# Greenhouse_Schematics.net
KiCad netlist of a schematic drawn in EAGLE
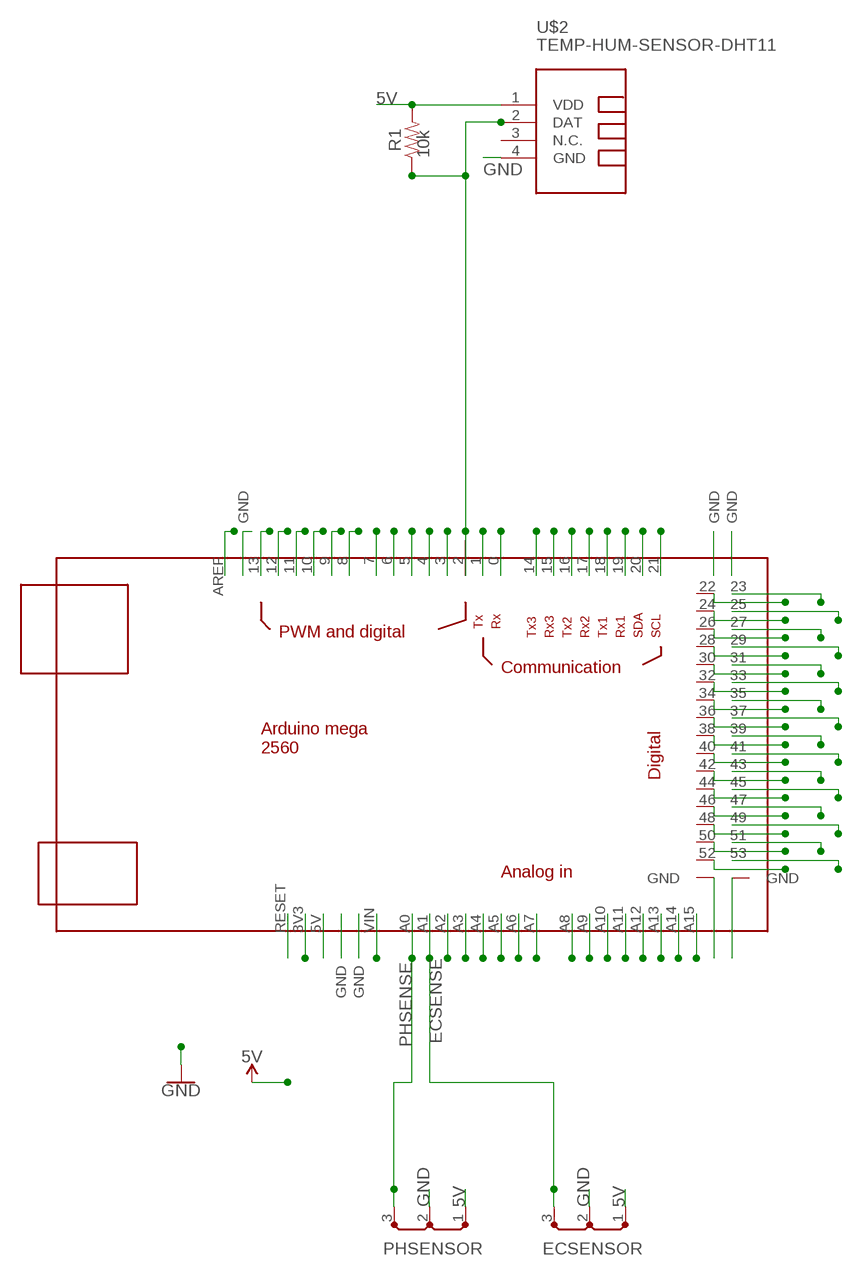
[diagram p0: schematic, sheet 1]

(export (version "E")
  (design (tool "Eeschema 10.0.6"))
  (components
    (comp (ref "BB1")
      (value "TE4/3")
      (footprint "eagle-import:TE4_3")
      (libsource (lib "eagle-import") (part "TE4/3"))
    )
    (comp (ref "BB2")
      (value "TE4/3")
      (footprint "eagle-import:TE4_3")
      (libsource (lib "eagle-import") (part "TE4/3"))
    )
    (comp (ref "R1")
      (value "RESISTORAXIAL-0.3")
      (footprint "eagle-import:AXIAL-0.3")
      (fields (field (name "PROD_ID") "10k"))
      (libsource (lib "eagle-import") (part "RESISTORAXIAL-0.3"))
    )
    (comp (ref "U$1")
      (value "MEGA_DEVICE")
      (footprint "eagle-import:MEGABOX")
      (libsource (lib "eagle-import") (part "MEGA_DEVICE"))
    )
    (comp (ref "U$2")
      (value "TEMP-HUM-SENSOR-DHT11")
      (footprint "eagle-import:TEMP-HUM-SENSOR-DHT11")
      (libsource (lib "eagle-import") (part "TEMP-HUM-SENSOR-DHT11"))
    )
  )
  (nets
    (net (code "1") (name "/ECSENSE") (class "Default")
      (node (ref "BB2") (pin "3") (pinfunction "P_3") (pintype "passive"))
      (node (ref "U$1") (pin "A1") (pinfunction "A1_A1") (pintype "bidirectional"))
    )
    (net (code "2") (name "/PHSENSE") (class "Default")
      (node (ref "BB1") (pin "3") (pinfunction "P_3") (pintype "passive"))
      (node (ref "U$1") (pin "A0") (pinfunction "A0_A0") (pintype "bidirectional"))
    )
    (net (code "3") (name "5V") (class "Default")
      (node (ref "BB1") (pin "1") (pinfunction "P_1") (pintype "passive"))
      (node (ref "BB2") (pin "1") (pinfunction "P_1") (pintype "passive"))
      (node (ref "R1") (pin "P$2") (pinfunction "2_P$2") (pintype "passive"))
      (node (ref "U$1") (pin "5V") (pinfunction "5V_5V") (pintype "bidirectional"))
      (node (ref "U$2") (pin "1") (pinfunction "VDD_1") (pintype "power_in"))
    )
    (net (code "4") (name "GND") (class "Default")
      (node (ref "BB1") (pin "2") (pinfunction "P_2") (pintype "passive"))
      (node (ref "BB2") (pin "2") (pinfunction "P_2") (pintype "passive"))
      (node (ref "U$1") (pin "GND@1") (pinfunction "GND_GND@1") (pintype "bidirectional"))
      (node (ref "U$1") (pin "GND@2") (pinfunction "GND_GND@2") (pintype "bidirectional"))
      (node (ref "U$1") (pin "GND@3") (pinfunction "GND_GND@3") (pintype "bidirectional"))
      (node (ref "U$1") (pin "GND@4") (pinfunction "GND_GND@4") (pintype "bidirectional"))
      (node (ref "U$1") (pin "GND@5") (pinfunction "GND_GND@5") (pintype "bidirectional"))
      (node (ref "U$1") (pin "GND@6") (pinfunction "GND_GND@6") (pintype "bidirectional"))
      (node (ref "U$1") (pin "GND@7") (pinfunction "GND_GND@7") (pintype "bidirectional"))
      (node (ref "U$2") (pin "4") (pinfunction "GND_4") (pintype "power_in"))
    )
    (net (code "5") (name "Net-(R1-1)") (class "Default")
      (node (ref "R1") (pin "P$1") (pinfunction "1_P$1") (pintype "passive"))
      (node (ref "U$1") (pin "2") (pinfunction "2_2") (pintype "bidirectional"))
      (node (ref "U$2") (pin "2") (pinfunction "DAT_2") (pintype "bidirectional"))
    )
    (net (code "6") (name "unconnected-(U$1-Pad0)") (class "Default")
      (node (ref "U$1") (pin "0") (pinfunction "0_0") (pintype "bidirectional"))
    )
    (net (code "7") (name "unconnected-(U$1-Pad1)") (class "Default")
      (node (ref "U$1") (pin "1") (pinfunction "1_1") (pintype "bidirectional"))
    )
    (net (code "8") (name "unconnected-(U$1-Pad3)") (class "Default")
      (node (ref "U$1") (pin "3") (pinfunction "3_3") (pintype "bidirectional"))
    )
    (net (code "9") (name "unconnected-(U$1-Pad3V3)") (class "Default")
      (node (ref "U$1") (pin "3V3") (pinfunction "3V3_3V3") (pintype "bidirectional"))
    )
    (net (code "10") (name "unconnected-(U$1-Pad4)") (class "Default")
      (node (ref "U$1") (pin "4") (pinfunction "4_4") (pintype "bidirectional"))
    )
    (net (code "11") (name "unconnected-(U$1-Pad5)") (class "Default")
      (node (ref "U$1") (pin "5") (pinfunction "5_5") (pintype "bidirectional"))
    )
    (net (code "12") (name "unconnected-(U$1-Pad6)") (class "Default")
      (node (ref "U$1") (pin "6") (pinfunction "6_6") (pintype "bidirectional"))
    )
    (net (code "13") (name "unconnected-(U$1-Pad7)") (class "Default")
      (node (ref "U$1") (pin "7") (pinfunction "7_7") (pintype "bidirectional"))
    )
    (net (code "14") (name "unconnected-(U$1-Pad8)") (class "Default")
      (node (ref "U$1") (pin "8") (pinfunction "8_8") (pintype "bidirectional"))
    )
    (net (code "15") (name "unconnected-(U$1-Pad9)") (class "Default")
      (node (ref "U$1") (pin "9") (pinfunction "9_9") (pintype "bidirectional"))
    )
    (net (code "16") (name "unconnected-(U$1-Pad10)") (class "Default")
      (node (ref "U$1") (pin "10") (pinfunction "10_10") (pintype "bidirectional"))
    )
    (net (code "17") (name "unconnected-(U$1-Pad11)") (class "Default")
      (node (ref "U$1") (pin "11") (pinfunction "11_11") (pintype "bidirectional"))
    )
    (net (code "18") (name "unconnected-(U$1-Pad12)") (class "Default")
      (node (ref "U$1") (pin "12") (pinfunction "12_12") (pintype "bidirectional"))
    )
    (net (code "19") (name "unconnected-(U$1-Pad13)") (class "Default")
      (node (ref "U$1") (pin "13") (pinfunction "13_13") (pintype "bidirectional"))
    )
    (net (code "20") (name "unconnected-(U$1-Pad14)") (class "Default")
      (node (ref "U$1") (pin "14") (pinfunction "14_14") (pintype "bidirectional"))
    )
    (net (code "21") (name "unconnected-(U$1-Pad15)") (class "Default")
      (node (ref "U$1") (pin "15") (pinfunction "15_15") (pintype "bidirectional"))
    )
    (net (code "22") (name "unconnected-(U$1-Pad16)") (class "Default")
      (node (ref "U$1") (pin "16") (pinfunction "16_16") (pintype "bidirectional"))
    )
    (net (code "23") (name "unconnected-(U$1-Pad17)") (class "Default")
      (node (ref "U$1") (pin "17") (pinfunction "17_17") (pintype "bidirectional"))
    )
    (net (code "24") (name "unconnected-(U$1-Pad18)") (class "Default")
      (node (ref "U$1") (pin "18") (pinfunction "18_18") (pintype "bidirectional"))
    )
    (net (code "25") (name "unconnected-(U$1-Pad19)") (class "Default")
      (node (ref "U$1") (pin "19") (pinfunction "19_19") (pintype "bidirectional"))
    )
    (net (code "26") (name "unconnected-(U$1-Pad20)") (class "Default")
      (node (ref "U$1") (pin "20") (pinfunction "20_20") (pintype "bidirectional"))
    )
    (net (code "27") (name "unconnected-(U$1-Pad21)") (class "Default")
      (node (ref "U$1") (pin "21") (pinfunction "21_21") (pintype "bidirectional"))
    )
    (net (code "28") (name "unconnected-(U$1-Pad22)") (class "Default")
      (node (ref "U$1") (pin "22") (pinfunction "22_22") (pintype "bidirectional"))
    )
    (net (code "29") (name "unconnected-(U$1-Pad23)") (class "Default")
      (node (ref "U$1") (pin "23") (pinfunction "23_23") (pintype "bidirectional"))
    )
    (net (code "30") (name "unconnected-(U$1-Pad24)") (class "Default")
      (node (ref "U$1") (pin "24") (pinfunction "24_24") (pintype "bidirectional"))
    )
    (net (code "31") (name "unconnected-(U$1-Pad25)") (class "Default")
      (node (ref "U$1") (pin "25") (pinfunction "25_25") (pintype "bidirectional"))
    )
    (net (code "32") (name "unconnected-(U$1-Pad26)") (class "Default")
      (node (ref "U$1") (pin "26") (pinfunction "26_26") (pintype "bidirectional"))
    )
    (net (code "33") (name "unconnected-(U$1-Pad27)") (class "Default")
      (node (ref "U$1") (pin "27") (pinfunction "27_27") (pintype "bidirectional"))
    )
    (net (code "34") (name "unconnected-(U$1-Pad28)") (class "Default")
      (node (ref "U$1") (pin "28") (pinfunction "28_28") (pintype "bidirectional"))
    )
    (net (code "35") (name "unconnected-(U$1-Pad29)") (class "Default")
      (node (ref "U$1") (pin "29") (pinfunction "29_29") (pintype "bidirectional"))
    )
    (net (code "36") (name "unconnected-(U$1-Pad30)") (class "Default")
      (node (ref "U$1") (pin "30") (pinfunction "30_30") (pintype "bidirectional"))
    )
    (net (code "37") (name "unconnected-(U$1-Pad31)") (class "Default")
      (node (ref "U$1") (pin "31") (pinfunction "31_31") (pintype "bidirectional"))
    )
    (net (code "38") (name "unconnected-(U$1-Pad32)") (class "Default")
      (node (ref "U$1") (pin "32") (pinfunction "32_32") (pintype "bidirectional"))
    )
    (net (code "39") (name "unconnected-(U$1-Pad33)") (class "Default")
      (node (ref "U$1") (pin "33") (pinfunction "33_33") (pintype "bidirectional"))
    )
    (net (code "40") (name "unconnected-(U$1-Pad34)") (class "Default")
      (node (ref "U$1") (pin "34") (pinfunction "34_34") (pintype "bidirectional"))
    )
    (net (code "41") (name "unconnected-(U$1-Pad35)") (class "Default")
      (node (ref "U$1") (pin "35") (pinfunction "35_35") (pintype "bidirectional"))
    )
    (net (code "42") (name "unconnected-(U$1-Pad36)") (class "Default")
      (node (ref "U$1") (pin "36") (pinfunction "36_36") (pintype "bidirectional"))
    )
    (net (code "43") (name "unconnected-(U$1-Pad37)") (class "Default")
      (node (ref "U$1") (pin "37") (pinfunction "37_37") (pintype "bidirectional"))
    )
    (net (code "44") (name "unconnected-(U$1-Pad38)") (class "Default")
      (node (ref "U$1") (pin "38") (pinfunction "38_38") (pintype "bidirectional"))
    )
    (net (code "45") (name "unconnected-(U$1-Pad39)") (class "Default")
      (node (ref "U$1") (pin "39") (pinfunction "39_39") (pintype "bidirectional"))
    )
    (net (code "46") (name "unconnected-(U$1-Pad40)") (class "Default")
      (node (ref "U$1") (pin "40") (pinfunction "40_40") (pintype "bidirectional"))
    )
    (net (code "47") (name "unconnected-(U$1-Pad41)") (class "Default")
      (node (ref "U$1") (pin "41") (pinfunction "41_41") (pintype "bidirectional"))
    )
    (net (code "48") (name "unconnected-(U$1-Pad42)") (class "Default")
      (node (ref "U$1") (pin "42") (pinfunction "42_42") (pintype "bidirectional"))
    )
    (net (code "49") (name "unconnected-(U$1-Pad43)") (class "Default")
      (node (ref "U$1") (pin "43") (pinfunction "43_43") (pintype "bidirectional"))
    )
    (net (code "50") (name "unconnected-(U$1-Pad44)") (class "Default")
      (node (ref "U$1") (pin "44") (pinfunction "44_44") (pintype "bidirectional"))
    )
    (net (code "51") (name "unconnected-(U$1-Pad45)") (class "Default")
      (node (ref "U$1") (pin "45") (pinfunction "45_45") (pintype "bidirectional"))
    )
    (net (code "52") (name "unconnected-(U$1-Pad46)") (class "Default")
      (node (ref "U$1") (pin "46") (pinfunction "46_46") (pintype "bidirectional"))
    )
    (net (code "53") (name "unconnected-(U$1-Pad47)") (class "Default")
      (node (ref "U$1") (pin "47") (pinfunction "47_47") (pintype "bidirectional"))
    )
    (net (code "54") (name "unconnected-(U$1-Pad48)") (class "Default")
      (node (ref "U$1") (pin "48") (pinfunction "48_48") (pintype "bidirectional"))
    )
    (net (code "55") (name "unconnected-(U$1-Pad49)") (class "Default")
      (node (ref "U$1") (pin "49") (pinfunction "49_49") (pintype "bidirectional"))
    )
    (net (code "56") (name "unconnected-(U$1-Pad50)") (class "Default")
      (node (ref "U$1") (pin "50") (pinfunction "50_50") (pintype "bidirectional"))
    )
    (net (code "57") (name "unconnected-(U$1-Pad51)") (class "Default")
      (node (ref "U$1") (pin "51") (pinfunction "51_51") (pintype "bidirectional"))
    )
    (net (code "58") (name "unconnected-(U$1-Pad52)") (class "Default")
      (node (ref "U$1") (pin "52") (pinfunction "52_52") (pintype "bidirectional"))
    )
    (net (code "59") (name "unconnected-(U$1-Pad53)") (class "Default")
      (node (ref "U$1") (pin "53") (pinfunction "53_53") (pintype "bidirectional"))
    )
    (net (code "60") (name "unconnected-(U$1-PadA2)") (class "Default")
      (node (ref "U$1") (pin "A2") (pinfunction "A2_A2") (pintype "bidirectional"))
    )
    (net (code "61") (name "unconnected-(U$1-PadA3)") (class "Default")
      (node (ref "U$1") (pin "A3") (pinfunction "A3_A3") (pintype "bidirectional"))
    )
    (net (code "62") (name "unconnected-(U$1-PadA4)") (class "Default")
      (node (ref "U$1") (pin "A4") (pinfunction "A4_A4") (pintype "bidirectional"))
    )
    (net (code "63") (name "unconnected-(U$1-PadA5)") (class "Default")
      (node (ref "U$1") (pin "A5") (pinfunction "A5_A5") (pintype "bidirectional"))
    )
    (net (code "64") (name "unconnected-(U$1-PadA6)") (class "Default")
      (node (ref "U$1") (pin "A6") (pinfunction "A6_A6") (pintype "bidirectional"))
    )
    (net (code "65") (name "unconnected-(U$1-PadA7)") (class "Default")
      (node (ref "U$1") (pin "A7") (pinfunction "A7_A7") (pintype "bidirectional"))
    )
    (net (code "66") (name "unconnected-(U$1-PadA8)") (class "Default")
      (node (ref "U$1") (pin "A8") (pinfunction "A8_A8") (pintype "bidirectional"))
    )
    (net (code "67") (name "unconnected-(U$1-PadA9)") (class "Default")
      (node (ref "U$1") (pin "A9") (pinfunction "A9_A9") (pintype "bidirectional"))
    )
    (net (code "68") (name "unconnected-(U$1-PadA10)") (class "Default")
      (node (ref "U$1") (pin "A10") (pinfunction "A10_A10") (pintype "bidirectional"))
    )
    (net (code "69") (name "unconnected-(U$1-PadA11)") (class "Default")
      (node (ref "U$1") (pin "A11") (pinfunction "A11_A11") (pintype "bidirectional"))
    )
    (net (code "70") (name "unconnected-(U$1-PadA12)") (class "Default")
      (node (ref "U$1") (pin "A12") (pinfunction "A12_A12") (pintype "bidirectional"))
    )
    (net (code "71") (name "unconnected-(U$1-PadA13)") (class "Default")
      (node (ref "U$1") (pin "A13") (pinfunction "A13_A13") (pintype "bidirectional"))
    )
    (net (code "72") (name "unconnected-(U$1-PadA14)") (class "Default")
      (node (ref "U$1") (pin "A14") (pinfunction "A14_A14") (pintype "bidirectional"))
    )
    (net (code "73") (name "unconnected-(U$1-PadA15)") (class "Default")
      (node (ref "U$1") (pin "A15") (pinfunction "A15_A15") (pintype "bidirectional"))
    )
    (net (code "74") (name "unconnected-(U$1-PadAREF)") (class "Default")
      (node (ref "U$1") (pin "AREF") (pinfunction "AREF_AREF") (pintype "bidirectional"))
    )
    (net (code "75") (name "unconnected-(U$1-PadRESET)") (class "Default")
      (node (ref "U$1") (pin "RESET") (pinfunction "RESET_RESET") (pintype "bidirectional"))
    )
    (net (code "76") (name "unconnected-(U$1-PadVIN)") (class "Default")
      (node (ref "U$1") (pin "VIN") (pinfunction "VIN_VIN") (pintype "bidirectional"))
    )
    (net (code "77") (name "unconnected-(U$2-N.C.-Pad3)") (class "Default")
      (node (ref "U$2") (pin "3") (pinfunction "N.C._3") (pintype "passive"))
    )
  )
)
